# Carte_compl_te.net
KiCad netlist of a schematic drawn in EAGLE
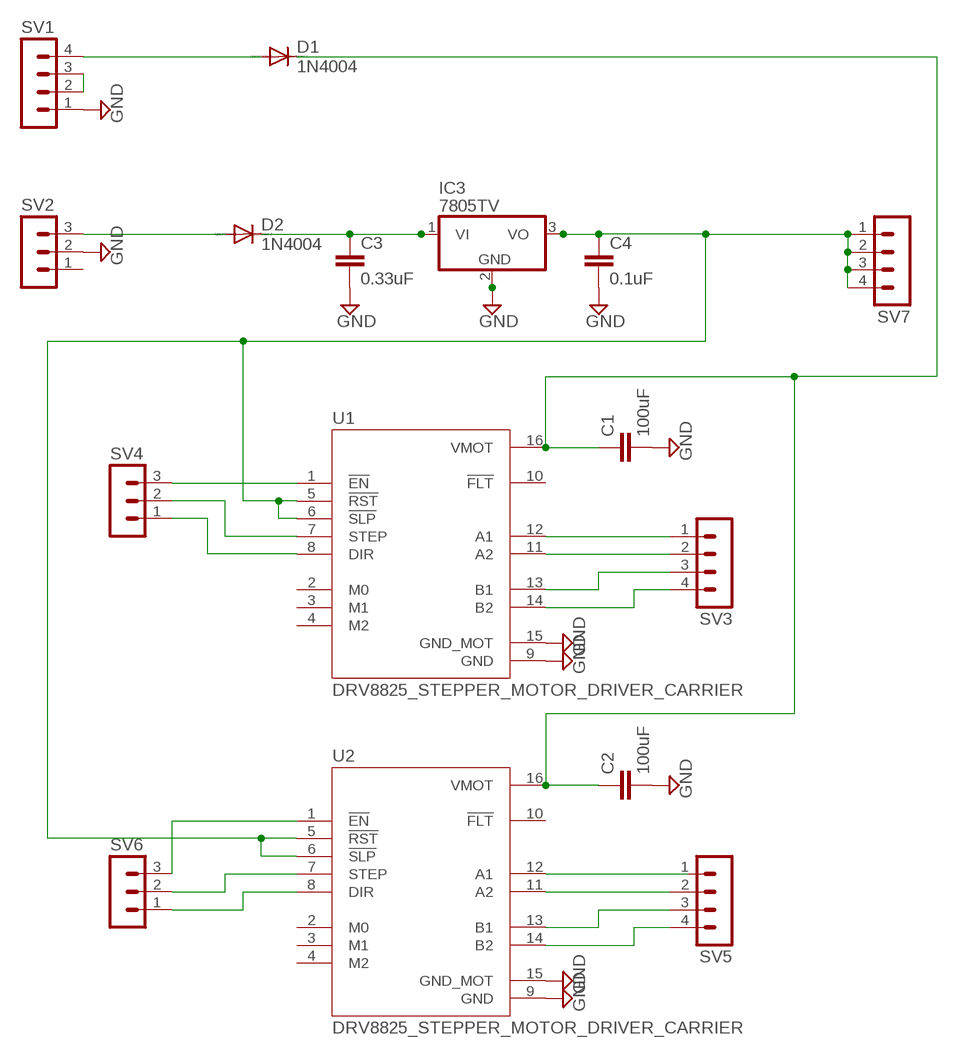
[diagram p0: schematic, sheet 1]

(export (version "E")
  (design (tool "Eeschema 10.0.6"))
  (components
    (comp (ref "C1")
      (value "100uF")
      (footprint "eagle-import:C025-024X044")
      (libsource (lib "eagle-import") (part "C-EU025-024X044"))
    )
    (comp (ref "C2")
      (value "100uF")
      (footprint "eagle-import:C025-024X044")
      (libsource (lib "eagle-import") (part "C-EU025-024X044"))
    )
    (comp (ref "C3")
      (value "0.33uF")
      (footprint "eagle-import:C025-024X044")
      (libsource (lib "eagle-import") (part "C-EU025-024X044"))
    )
    (comp (ref "C4")
      (value "0.1uF")
      (footprint "eagle-import:C025-024X044")
      (libsource (lib "eagle-import") (part "C-EU025-024X044"))
    )
    (comp (ref "D1")
      (value "1N4004")
      (footprint "eagle-import:DO41-10")
      (libsource (lib "eagle-import") (part "1N4004"))
    )
    (comp (ref "D2")
      (value "1N4004")
      (footprint "eagle-import:DO41-10")
      (libsource (lib "eagle-import") (part "1N4004"))
    )
    (comp (ref "IC3")
      (value "7805TV")
      (footprint "eagle-import:TO220V")
      (libsource (lib "eagle-import") (part "78TV05"))
    )
    (comp (ref "SV1")
      (value "MA04-1")
      (footprint "eagle-import:MA04-1")
      (libsource (lib "eagle-import") (part "MA04-1"))
    )
    (comp (ref "SV2")
      (value "MA03-1")
      (footprint "eagle-import:MA03-1")
      (libsource (lib "eagle-import") (part "MA03-1"))
    )
    (comp (ref "SV3")
      (value "MA04-1")
      (footprint "eagle-import:MA04-1")
      (libsource (lib "eagle-import") (part "MA04-1"))
    )
    (comp (ref "SV4")
      (value "MA03-1")
      (footprint "eagle-import:MA03-1")
      (libsource (lib "eagle-import") (part "MA03-1"))
    )
    (comp (ref "SV5")
      (value "MA04-1")
      (footprint "eagle-import:MA04-1")
      (libsource (lib "eagle-import") (part "MA04-1"))
    )
    (comp (ref "SV6")
      (value "MA03-1")
      (footprint "eagle-import:MA03-1")
      (libsource (lib "eagle-import") (part "MA03-1"))
    )
    (comp (ref "SV7")
      (value "MA04-1")
      (footprint "eagle-import:MA04-1")
      (libsource (lib "eagle-import") (part "MA04-1"))
    )
    (comp (ref "U1")
      (value "DRV8825_STEPPER_MOTOR_DRIVER_CARRIER")
      (footprint "eagle-import:IC_DRV8825_STEPPER_MOTOR_DRIVER_CARRIER")
      (fields (field (name "MF") "Pololu") (field (name "MP") "DRV8825 STEPPER MOTOR DRIVER CARRIER"))
      (libsource (lib "eagle-import") (part "DRV8825_STEPPER_MOTOR_DRIVER_CARRIER"))
    )
    (comp (ref "U2")
      (value "DRV8825_STEPPER_MOTOR_DRIVER_CARRIER")
      (footprint "eagle-import:IC_DRV8825_STEPPER_MOTOR_DRIVER_CARRIER")
      (fields (field (name "MF") "Pololu") (field (name "MP") "DRV8825 STEPPER MOTOR DRIVER CARRIER"))
      (libsource (lib "eagle-import") (part "DRV8825_STEPPER_MOTOR_DRIVER_CARRIER"))
    )
  )
  (nets
    (net (code "1") (name "GND") (class "Default")
      (node (ref "C1") (pin "2") (pinfunction "2_2") (pintype "passive"))
      (node (ref "C2") (pin "2") (pinfunction "2_2") (pintype "passive"))
      (node (ref "C3") (pin "2") (pinfunction "2_2") (pintype "passive"))
      (node (ref "C4") (pin "2") (pinfunction "2_2") (pintype "passive"))
      (node (ref "IC3") (pin "2") (pinfunction "GND_2") (pintype "passive"))
      (node (ref "SV1") (pin "1") (pinfunction "1_1") (pintype "passive"))
      (node (ref "SV2") (pin "2") (pinfunction "2_2") (pintype "passive"))
      (node (ref "U1") (pin "15") (pinfunction "GND_MOT_15") (pintype "power_in"))
      (node (ref "U1") (pin "9") (pinfunction "GND_9") (pintype "power_in"))
      (node (ref "U2") (pin "15") (pinfunction "GND_MOT_15") (pintype "power_in"))
      (node (ref "U2") (pin "9") (pinfunction "GND_9") (pintype "power_in"))
    )
    (net (code "2") (name "Net-(D1-PadA)") (class "Default")
      (node (ref "D1") (pin "A") (pinfunction "A_A") (pintype "passive"))
      (node (ref "SV1") (pin "4") (pinfunction "4_4") (pintype "passive"))
    )
    (net (code "3") (name "Net-(D2-PadA)") (class "Default")
      (node (ref "D2") (pin "A") (pinfunction "A_A") (pintype "passive"))
      (node (ref "SV2") (pin "3") (pinfunction "3_3") (pintype "passive"))
    )
    (net (code "4") (name "Net-(IC3-VI)") (class "Default")
      (node (ref "C3") (pin "1") (pinfunction "1_1") (pintype "passive"))
      (node (ref "D2") (pin "C") (pinfunction "C_C") (pintype "passive"))
      (node (ref "IC3") (pin "1") (pinfunction "VI_1") (pintype "input"))
    )
    (net (code "5") (name "Net-(IC3-VO)") (class "Default")
      (node (ref "C4") (pin "1") (pinfunction "1_1") (pintype "passive"))
      (node (ref "IC3") (pin "3") (pinfunction "VO_3") (pintype "passive"))
      (node (ref "SV7") (pin "1") (pinfunction "1_1") (pintype "passive"))
      (node (ref "SV7") (pin "2") (pinfunction "2_2") (pintype "passive"))
      (node (ref "SV7") (pin "3") (pinfunction "3_3") (pintype "passive"))
      (node (ref "SV7") (pin "4") (pinfunction "4_4") (pintype "passive"))
      (node (ref "U1") (pin "5") (pinfunction "~{RST}_5") (pintype "input"))
      (node (ref "U1") (pin "6") (pinfunction "~{SLP}_6") (pintype "input"))
      (node (ref "U2") (pin "5") (pinfunction "~{RST}_5") (pintype "input"))
      (node (ref "U2") (pin "6") (pinfunction "~{SLP}_6") (pintype "input"))
    )
    (net (code "6") (name "Net-(SV1-Pad2)") (class "Default")
      (node (ref "SV1") (pin "2") (pinfunction "2_2") (pintype "passive"))
      (node (ref "SV1") (pin "3") (pinfunction "3_3") (pintype "passive"))
    )
    (net (code "7") (name "Net-(U1-A1)") (class "Default")
      (node (ref "SV3") (pin "1") (pinfunction "1_1") (pintype "passive"))
      (node (ref "U1") (pin "12") (pinfunction "A1_12") (pintype "output"))
    )
    (net (code "8") (name "Net-(U1-A2)") (class "Default")
      (node (ref "SV3") (pin "2") (pinfunction "2_2") (pintype "passive"))
      (node (ref "U1") (pin "11") (pinfunction "A2_11") (pintype "output"))
    )
    (net (code "9") (name "Net-(U1-B1)") (class "Default")
      (node (ref "SV3") (pin "3") (pinfunction "3_3") (pintype "passive"))
      (node (ref "U1") (pin "13") (pinfunction "B1_13") (pintype "output"))
    )
    (net (code "10") (name "Net-(U1-B2)") (class "Default")
      (node (ref "SV3") (pin "4") (pinfunction "4_4") (pintype "passive"))
      (node (ref "U1") (pin "14") (pinfunction "B2_14") (pintype "output"))
    )
    (net (code "11") (name "Net-(U1-DIR)") (class "Default")
      (node (ref "SV4") (pin "1") (pinfunction "1_1") (pintype "passive"))
      (node (ref "U1") (pin "8") (pinfunction "DIR_8") (pintype "input"))
    )
    (net (code "12") (name "Net-(U1-STEP)") (class "Default")
      (node (ref "SV4") (pin "2") (pinfunction "2_2") (pintype "passive"))
      (node (ref "U1") (pin "7") (pinfunction "STEP_7") (pintype "input"))
    )
    (net (code "13") (name "Net-(U1-VMOT)") (class "Default")
      (node (ref "C1") (pin "1") (pinfunction "1_1") (pintype "passive"))
      (node (ref "C2") (pin "1") (pinfunction "1_1") (pintype "passive"))
      (node (ref "D1") (pin "C") (pinfunction "C_C") (pintype "passive"))
      (node (ref "U1") (pin "16") (pinfunction "VMOT_16") (pintype "power_in"))
      (node (ref "U2") (pin "16") (pinfunction "VMOT_16") (pintype "power_in"))
    )
    (net (code "14") (name "Net-(U1-~{EN})") (class "Default")
      (node (ref "SV4") (pin "3") (pinfunction "3_3") (pintype "passive"))
      (node (ref "U1") (pin "1") (pinfunction "~{EN}_1") (pintype "input"))
    )
    (net (code "15") (name "Net-(U2-A2)") (class "Default")
      (node (ref "SV5") (pin "2") (pinfunction "2_2") (pintype "passive"))
      (node (ref "U2") (pin "11") (pinfunction "A2_11") (pintype "output"))
    )
    (net (code "16") (name "Net-(U2-B1)") (class "Default")
      (node (ref "SV5") (pin "3") (pinfunction "3_3") (pintype "passive"))
      (node (ref "U2") (pin "13") (pinfunction "B1_13") (pintype "output"))
    )
    (net (code "17") (name "Net-(U2-B2)") (class "Default")
      (node (ref "SV5") (pin "4") (pinfunction "4_4") (pintype "passive"))
      (node (ref "U2") (pin "14") (pinfunction "B2_14") (pintype "output"))
    )
    (net (code "18") (name "Net-(U2-DIR)") (class "Default")
      (node (ref "SV6") (pin "1") (pinfunction "1_1") (pintype "passive"))
      (node (ref "U2") (pin "8") (pinfunction "DIR_8") (pintype "input"))
    )
    (net (code "19") (name "Net-(U2-STEP)") (class "Default")
      (node (ref "SV6") (pin "2") (pinfunction "2_2") (pintype "passive"))
      (node (ref "U2") (pin "7") (pinfunction "STEP_7") (pintype "input"))
    )
    (net (code "20") (name "Net-(U2-~{EN})") (class "Default")
      (node (ref "SV6") (pin "3") (pinfunction "3_3") (pintype "passive"))
      (node (ref "U2") (pin "1") (pinfunction "~{EN}_1") (pintype "input"))
    )
    (net (code "21") (name "unconnected-(SV2-Pad1)") (class "Default")
      (node (ref "SV2") (pin "1") (pinfunction "1_1") (pintype "passive"))
    )
    (net (code "22") (name "unconnected-(SV5-Pad1)") (class "Default")
      (node (ref "SV5") (pin "1") (pinfunction "1_1") (pintype "passive"))
    )
    (net (code "23") (name "unconnected-(U1-M0-Pad2)") (class "Default")
      (node (ref "U1") (pin "2") (pinfunction "M0_2") (pintype "input"))
    )
    (net (code "24") (name "unconnected-(U1-M1-Pad3)") (class "Default")
      (node (ref "U1") (pin "3") (pinfunction "M1_3") (pintype "input"))
    )
    (net (code "25") (name "unconnected-(U1-M2-Pad4)") (class "Default")
      (node (ref "U1") (pin "4") (pinfunction "M2_4") (pintype "input"))
    )
    (net (code "26") (name "unconnected-(U1-~{FLT}-Pad10)") (class "Default")
      (node (ref "U1") (pin "10") (pinfunction "~{FLT}_10") (pintype "output"))
    )
    (net (code "27") (name "unconnected-(U2-A1-Pad12)") (class "Default")
      (node (ref "U2") (pin "12") (pinfunction "A1_12") (pintype "output"))
    )
    (net (code "28") (name "unconnected-(U2-M0-Pad2)") (class "Default")
      (node (ref "U2") (pin "2") (pinfunction "M0_2") (pintype "input"))
    )
    (net (code "29") (name "unconnected-(U2-M1-Pad3)") (class "Default")
      (node (ref "U2") (pin "3") (pinfunction "M1_3") (pintype "input"))
    )
    (net (code "30") (name "unconnected-(U2-M2-Pad4)") (class "Default")
      (node (ref "U2") (pin "4") (pinfunction "M2_4") (pintype "input"))
    )
    (net (code "31") (name "unconnected-(U2-~{FLT}-Pad10)") (class "Default")
      (node (ref "U2") (pin "10") (pinfunction "~{FLT}_10") (pintype "output"))
    )
  )
)
